# Soil_Moisture_Sensor_Pro_Mini.net
KiCad netlist of a schematic drawn in EAGLE
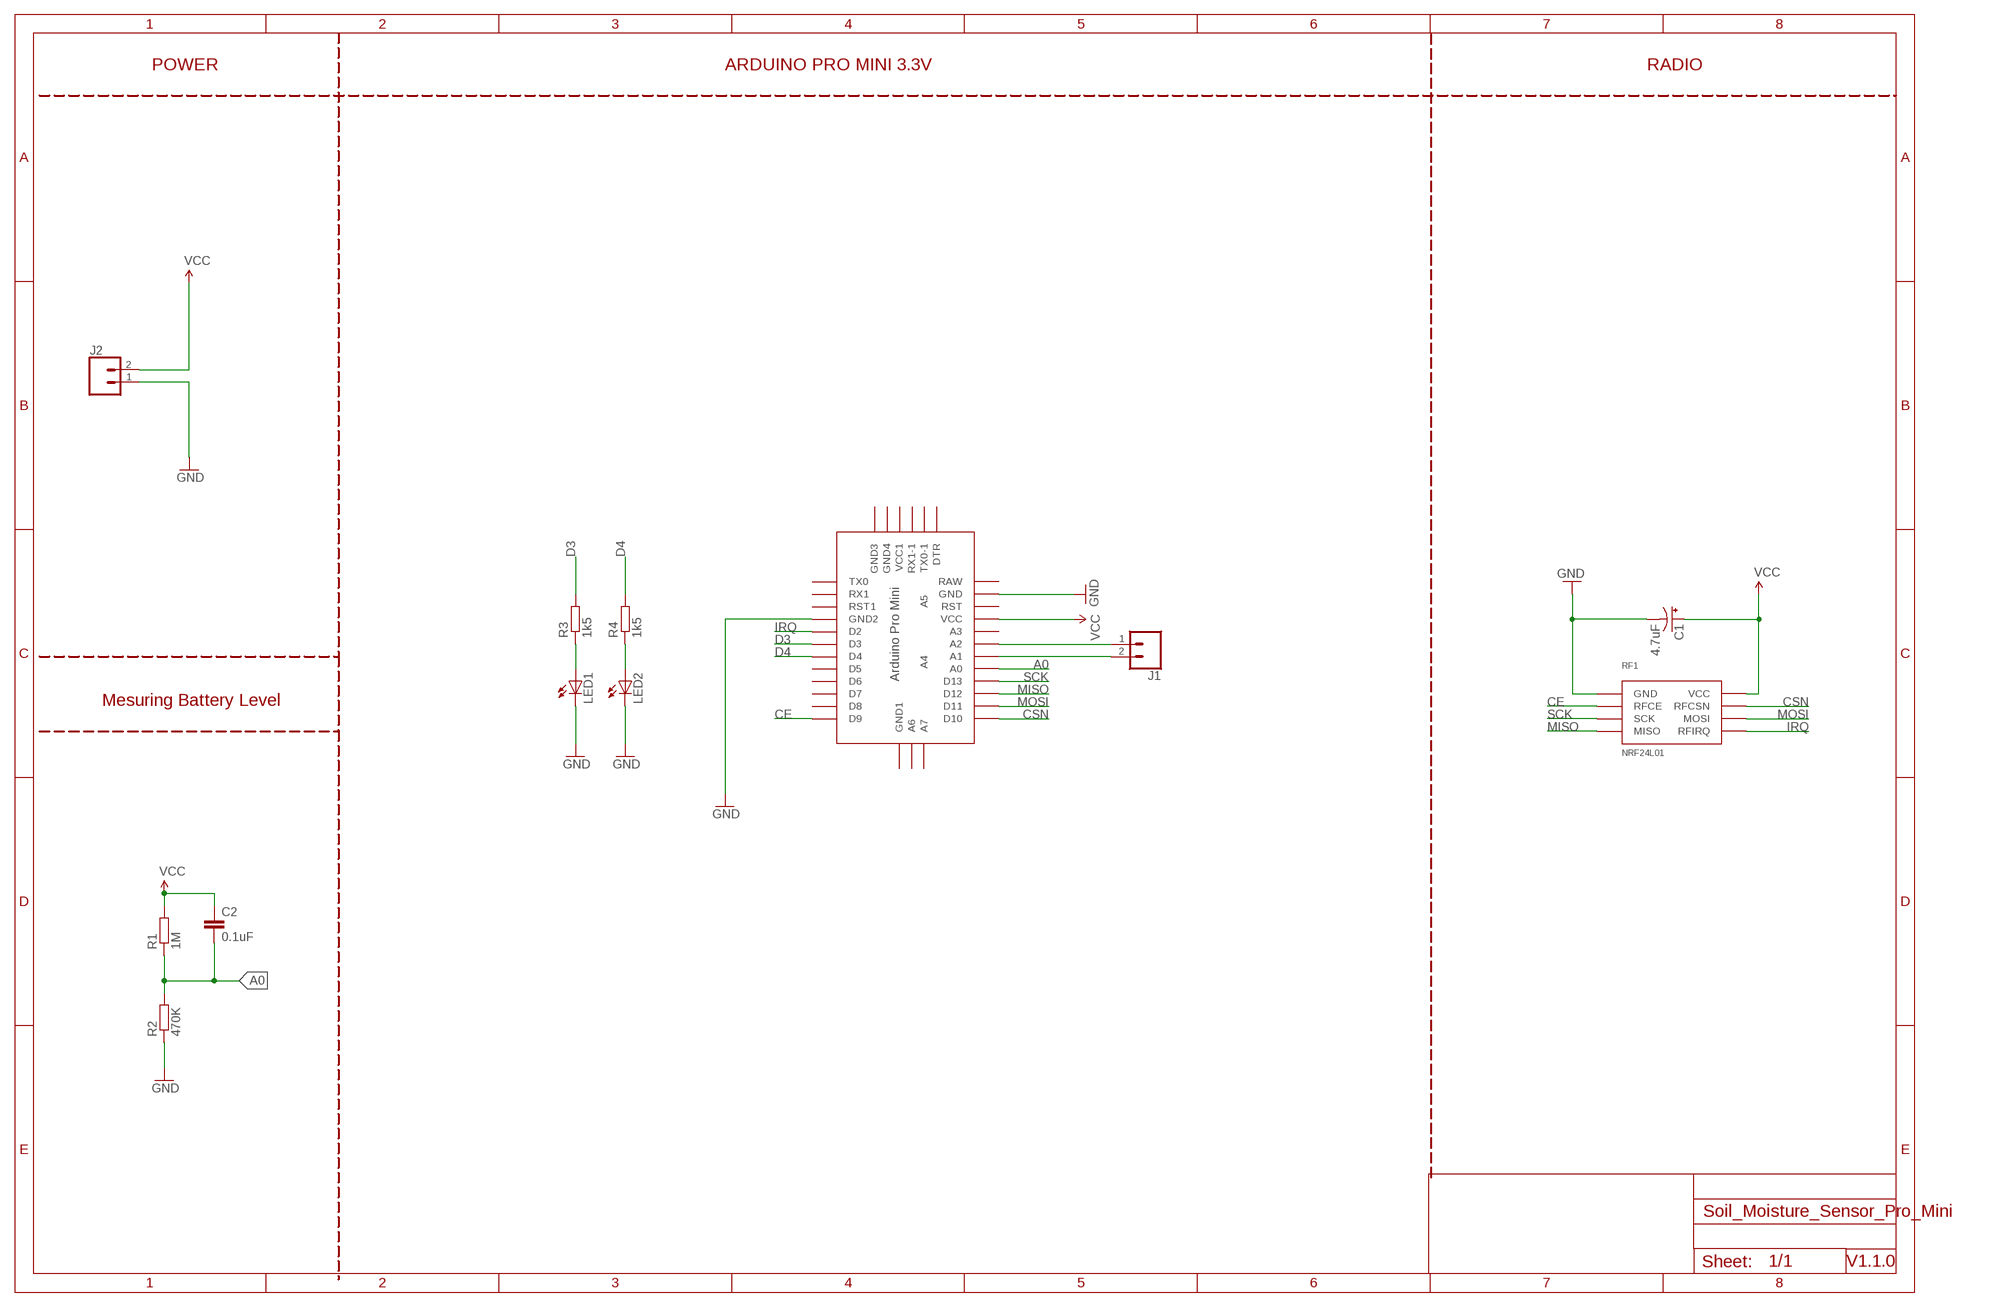
[diagram p0: schematic, sheet 1]

(export (version "E")
  (design (tool "Eeschema 10.0.6"))
  (components
    (comp (ref "C1")
      (value "4.7uF")
      (footprint "eagle-import:E2,5-6E")
      (libsource (lib "eagle-import") (part "CPOL-USE2,5-6E"))
    )
    (comp (ref "C2")
      (value "0.1uF")
      (footprint "eagle-import:C025-025X050")
      (libsource (lib "eagle-import") (part "C-EU025-025X050"))
    )
    (comp (ref "J1")
      (value "CONN_02")
      (footprint "eagle-import:1X02")
      (libsource (lib "eagle-import") (part "CONN_02"))
    )
    (comp (ref "J2")
      (value "CONN_02")
      (footprint "eagle-import:1X02")
      (libsource (lib "eagle-import") (part "CONN_02"))
    )
    (comp (ref "LED1")
      (value "LED3MM")
      (footprint "eagle-import:LED3MM")
      (libsource (lib "eagle-import") (part "LED3MM"))
    )
    (comp (ref "LED2")
      (value "LED3MM")
      (footprint "eagle-import:LED3MM")
      (libsource (lib "eagle-import") (part "LED3MM"))
    )
    (comp (ref "R1")
      (value "1M")
      (footprint "eagle-import:0204_7")
      (libsource (lib "eagle-import") (part "R-EU_0204/7"))
    )
    (comp (ref "R2")
      (value "470K")
      (footprint "eagle-import:0204_7")
      (libsource (lib "eagle-import") (part "R-EU_0204/7"))
    )
    (comp (ref "R3")
      (value "1k5")
      (footprint "eagle-import:0204_7")
      (libsource (lib "eagle-import") (part "R-EU_0204/7"))
    )
    (comp (ref "R4")
      (value "1k5")
      (footprint "eagle-import:0204_7")
      (libsource (lib "eagle-import") (part "R-EU_0204/7"))
    )
    (comp (ref "RF1")
      (value "NRF24L01")
      (footprint "eagle-import:2X4-2.54MM")
      (libsource (lib "eagle-import") (part "NRF24L01"))
    )
    (comp (ref "U$1")
      (value "ABK-PRO-MINI")
      (footprint "eagle-import:ABK-PRO-MINI")
      (libsource (lib "eagle-import") (part "ABK-PRO-MINI"))
    )
  )
  (nets
    (net (code "1") (name "/CE") (class "Default")
      (node (ref "RF1") (pin "P$3") (pinfunction "RFCE_P$3") (pintype "input"))
      (node (ref "U$1") (pin "D9") (pinfunction "D9_D9") (pintype "bidirectional"))
    )
    (net (code "2") (name "/CSN") (class "Default")
      (node (ref "RF1") (pin "P$4") (pinfunction "RFCSN_P$4") (pintype "bidirectional"))
      (node (ref "U$1") (pin "D10") (pinfunction "D10_D10") (pintype "bidirectional"))
    )
    (net (code "3") (name "/D3") (class "Default")
      (node (ref "R3") (pin "2") (pinfunction "2_2") (pintype "passive"))
      (node (ref "U$1") (pin "D3") (pinfunction "D3_D3") (pintype "bidirectional"))
    )
    (net (code "4") (name "/D4") (class "Default")
      (node (ref "R4") (pin "2") (pinfunction "2_2") (pintype "passive"))
      (node (ref "U$1") (pin "D4") (pinfunction "D4_D4") (pintype "bidirectional"))
    )
    (net (code "5") (name "/IRQ") (class "Default")
      (node (ref "RF1") (pin "P$8") (pinfunction "RFIRQ_P$8") (pintype "output"))
      (node (ref "U$1") (pin "D2") (pinfunction "D2_D2") (pintype "bidirectional"))
    )
    (net (code "6") (name "/MISO") (class "Default")
      (node (ref "RF1") (pin "P$7") (pinfunction "MISO_P$7") (pintype "bidirectional"))
      (node (ref "U$1") (pin "D12") (pinfunction "D12_D12") (pintype "bidirectional"))
    )
    (net (code "7") (name "/MOSI") (class "Default")
      (node (ref "RF1") (pin "P$6") (pinfunction "MOSI_P$6") (pintype "bidirectional"))
      (node (ref "U$1") (pin "D11") (pinfunction "D11_D11") (pintype "bidirectional"))
    )
    (net (code "8") (name "/SCK") (class "Default")
      (node (ref "RF1") (pin "P$5") (pinfunction "SCK_P$5") (pintype "input"))
      (node (ref "U$1") (pin "D13") (pinfunction "D13_D13") (pintype "bidirectional"))
    )
    (net (code "9") (name "A0") (class "Default")
      (node (ref "C2") (pin "2") (pinfunction "2_2") (pintype "passive"))
      (node (ref "R1") (pin "1") (pinfunction "1_1") (pintype "passive"))
      (node (ref "R2") (pin "2") (pinfunction "2_2") (pintype "passive"))
      (node (ref "U$1") (pin "A0") (pinfunction "A0_A0") (pintype "bidirectional"))
    )
    (net (code "10") (name "GND") (class "Default")
      (node (ref "C1") (pin "-") (pinfunction "-_-") (pintype "passive"))
      (node (ref "J2") (pin "1") (pinfunction "1_1") (pintype "passive"))
      (node (ref "LED1") (pin "K") (pinfunction "C_K") (pintype "passive"))
      (node (ref "LED2") (pin "K") (pinfunction "C_K") (pintype "passive"))
      (node (ref "R2") (pin "1") (pinfunction "1_1") (pintype "passive"))
      (node (ref "RF1") (pin "P$1") (pinfunction "GND_P$1") (pintype "power_in"))
      (node (ref "U$1") (pin "GND") (pinfunction "GND_GND") (pintype "bidirectional"))
      (node (ref "U$1") (pin "GND1") (pinfunction "GND2_GND1") (pintype "bidirectional"))
    )
    (net (code "11") (name "Net-(J1-Pad1)") (class "Default")
      (node (ref "J1") (pin "1") (pinfunction "1_1") (pintype "passive"))
      (node (ref "U$1") (pin "A2") (pinfunction "A2_A2") (pintype "bidirectional"))
    )
    (net (code "12") (name "Net-(J1-Pad2)") (class "Default")
      (node (ref "J1") (pin "2") (pinfunction "2_2") (pintype "passive"))
      (node (ref "U$1") (pin "A1") (pinfunction "A1_A1") (pintype "bidirectional"))
    )
    (net (code "13") (name "Net-(LED1-PadA)") (class "Default")
      (node (ref "LED1") (pin "A") (pinfunction "A_A") (pintype "passive"))
      (node (ref "R3") (pin "1") (pinfunction "1_1") (pintype "passive"))
    )
    (net (code "14") (name "Net-(LED2-PadA)") (class "Default")
      (node (ref "LED2") (pin "A") (pinfunction "A_A") (pintype "passive"))
      (node (ref "R4") (pin "1") (pinfunction "1_1") (pintype "passive"))
    )
    (net (code "15") (name "VCC") (class "Default")
      (node (ref "C1") (pin "+") (pinfunction "+_+") (pintype "passive"))
      (node (ref "C2") (pin "1") (pinfunction "1_1") (pintype "passive"))
      (node (ref "J2") (pin "2") (pinfunction "2_2") (pintype "passive"))
      (node (ref "R1") (pin "2") (pinfunction "2_2") (pintype "passive"))
      (node (ref "RF1") (pin "P$2") (pinfunction "VCC_P$2") (pintype "power_in"))
      (node (ref "U$1") (pin "VCC") (pinfunction "VCC_VCC") (pintype "bidirectional"))
    )
    (net (code "16") (name "unconnected-(U$1-GND1-PadGND4)") (class "Default")
      (node (ref "U$1") (pin "GND4") (pinfunction "GND1_GND4") (pintype "bidirectional"))
    )
    (net (code "17") (name "unconnected-(U$1-GND3-PadGND2)") (class "Default")
      (node (ref "U$1") (pin "GND2") (pinfunction "GND3_GND2") (pintype "bidirectional"))
    )
    (net (code "18") (name "unconnected-(U$1-GND4-PadGND3)") (class "Default")
      (node (ref "U$1") (pin "GND3") (pinfunction "GND4_GND3") (pintype "bidirectional"))
    )
    (net (code "19") (name "unconnected-(U$1-PadA3)") (class "Default")
      (node (ref "U$1") (pin "A3") (pinfunction "A3_A3") (pintype "bidirectional"))
    )
    (net (code "20") (name "unconnected-(U$1-PadA4)") (class "Default")
      (node (ref "U$1") (pin "A4") (pinfunction "A4_A4") (pintype "bidirectional"))
    )
    (net (code "21") (name "unconnected-(U$1-PadA5)") (class "Default")
      (node (ref "U$1") (pin "A5") (pinfunction "A5_A5") (pintype "bidirectional"))
    )
    (net (code "22") (name "unconnected-(U$1-PadA6)") (class "Default")
      (node (ref "U$1") (pin "A6") (pinfunction "A6_A6") (pintype "bidirectional"))
    )
    (net (code "23") (name "unconnected-(U$1-PadA7)") (class "Default")
      (node (ref "U$1") (pin "A7") (pinfunction "A7_A7") (pintype "bidirectional"))
    )
    (net (code "24") (name "unconnected-(U$1-PadD5)") (class "Default")
      (node (ref "U$1") (pin "D5") (pinfunction "D5_D5") (pintype "bidirectional"))
    )
    (net (code "25") (name "unconnected-(U$1-PadD6)") (class "Default")
      (node (ref "U$1") (pin "D6") (pinfunction "D6_D6") (pintype "bidirectional"))
    )
    (net (code "26") (name "unconnected-(U$1-PadD7)") (class "Default")
      (node (ref "U$1") (pin "D7") (pinfunction "D7_D7") (pintype "bidirectional"))
    )
    (net (code "27") (name "unconnected-(U$1-PadD8)") (class "Default")
      (node (ref "U$1") (pin "D8") (pinfunction "D8_D8") (pintype "bidirectional"))
    )
    (net (code "28") (name "unconnected-(U$1-PadDTR)") (class "Default")
      (node (ref "U$1") (pin "DTR") (pinfunction "DTR_DTR") (pintype "bidirectional"))
    )
    (net (code "29") (name "unconnected-(U$1-PadRAW)") (class "Default")
      (node (ref "U$1") (pin "RAW") (pinfunction "RAW_RAW") (pintype "bidirectional"))
    )
    (net (code "30") (name "unconnected-(U$1-PadRST)") (class "Default")
      (node (ref "U$1") (pin "RST") (pinfunction "RST_RST") (pintype "bidirectional"))
    )
    (net (code "31") (name "unconnected-(U$1-PadRST1)") (class "Default")
      (node (ref "U$1") (pin "RST1") (pinfunction "RST1_RST1") (pintype "bidirectional"))
    )
    (net (code "32") (name "unconnected-(U$1-PadRX1)") (class "Default")
      (node (ref "U$1") (pin "RX1") (pinfunction "RX1_RX1") (pintype "bidirectional"))
    )
    (net (code "33") (name "unconnected-(U$1-PadRX1-1)") (class "Default")
      (node (ref "U$1") (pin "RX1-1") (pinfunction "RX1-1_RX1-1") (pintype "bidirectional"))
    )
    (net (code "34") (name "unconnected-(U$1-PadTX0)") (class "Default")
      (node (ref "U$1") (pin "TX0") (pinfunction "TX0_TX0") (pintype "bidirectional"))
    )
    (net (code "35") (name "unconnected-(U$1-PadTX0-1)") (class "Default")
      (node (ref "U$1") (pin "TX0-1") (pinfunction "TX0-1_TX0-1") (pintype "bidirectional"))
    )
    (net (code "36") (name "unconnected-(U$1-PadVCC1)") (class "Default")
      (node (ref "U$1") (pin "VCC1") (pinfunction "VCC1_VCC1") (pintype "bidirectional"))
    )
  )
)
